# BT-5.net
KiCad netlist of a schematic drawn in EAGLE
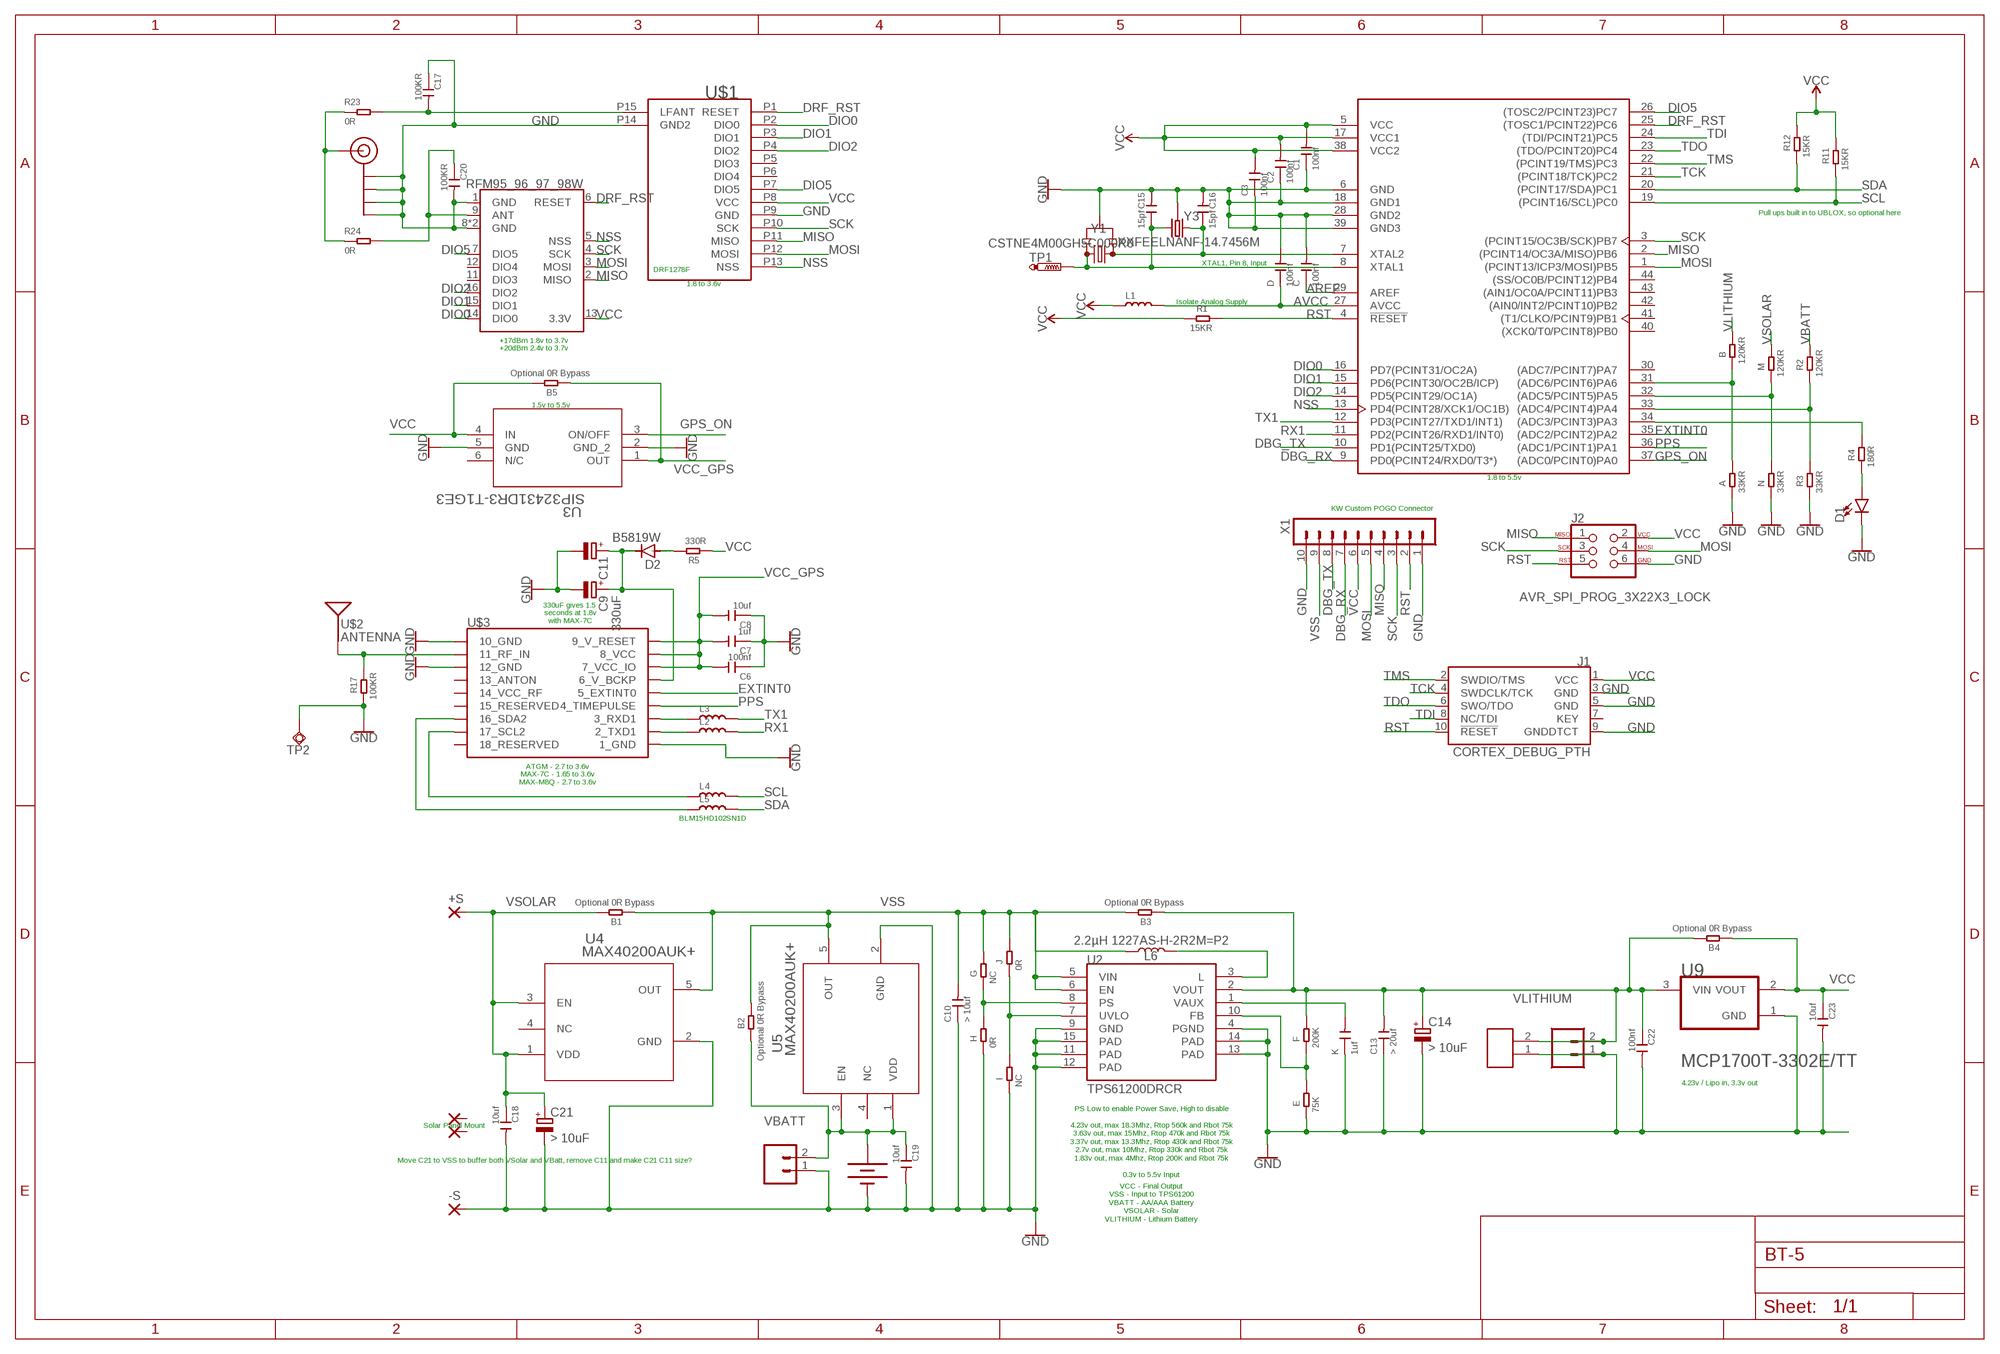
[diagram p0: schematic, sheet 1]

(export (version "E")
  (design (tool "Eeschema 10.0.6"))
  (components
    (comp (ref "+S")
      (value "SMD2")
      (footprint "eagle-import:SMD1,27-2,54")
      (libsource (lib "eagle-import") (part "SMD2"))
    )
    (comp (ref "-S")
      (value "SMD2")
      (footprint "eagle-import:SMD1,27-2,54")
      (libsource (lib "eagle-import") (part "SMD2"))
    )
    (comp (ref "A")
      (value "33KR")
      (footprint "eagle-import:R0402")
      (fields (field (name "MPN") "RC0402JR-070RL"))
      (libsource (lib "eagle-import") (part "SMD-RES-20K-5%-1/16W(0402)"))
    )
    (comp (ref "B")
      (value "120KR")
      (footprint "eagle-import:R0402")
      (fields (field (name "MPN") "RC0402JR-070RL"))
      (libsource (lib "eagle-import") (part "SMD-RES-20K-5%-1/16W(0402)"))
    )
    (comp (ref "B1")
      (value "Optional 0R Bypass")
      (footprint "eagle-import:R0402")
      (fields (field (name "MPN") "RC0402JR-070RL"))
      (libsource (lib "eagle-import") (part "SMD-RES-20K-5%-1/16W(0402)"))
    )
    (comp (ref "B2")
      (value "Optional 0R Bypass")
      (footprint "eagle-import:R0402")
      (fields (field (name "MPN") "RC0402JR-070RL"))
      (libsource (lib "eagle-import") (part "SMD-RES-20K-5%-1/16W(0402)"))
    )
    (comp (ref "B3")
      (value "Optional 0R Bypass")
      (footprint "eagle-import:R0402")
      (fields (field (name "MPN") "RC0402JR-070RL"))
      (libsource (lib "eagle-import") (part "SMD-RES-20K-5%-1/16W(0402)"))
    )
    (comp (ref "B4")
      (value "Optional 0R Bypass")
      (footprint "eagle-import:R0402")
      (fields (field (name "MPN") "RC0402JR-070RL"))
      (libsource (lib "eagle-import") (part "SMD-RES-20K-5%-1/16W(0402)"))
    )
    (comp (ref "B5")
      (value "Optional 0R Bypass")
      (footprint "eagle-import:R0402")
      (fields (field (name "MPN") "RC0402JR-070RL"))
      (libsource (lib "eagle-import") (part "SMD-RES-20K-5%-1/16W(0402)"))
    )
    (comp (ref "BT1")
      (value "BATTERY")
      (footprint "eagle-import:BATTERY-AA-AAA")
      (libsource (lib "eagle-import") (part "BATTERY"))
    )
    (comp (ref "C")
      (value "100nf")
      (footprint "eagle-import:C0402")
      (fields (field (name "MPN") "CC0402KRX7R8BB104"))
      (libsource (lib "eagle-import") (part "CERAMIC-100NF-25V-10%-X7R(0402)"))
    )
    (comp (ref "C1")
      (value "100nf")
      (footprint "eagle-import:C0402")
      (fields (field (name "MPN") "CC0402KRX7R8BB104"))
      (libsource (lib "eagle-import") (part "CERAMIC-100NF-25V-10%-X7R(0402)"))
    )
    (comp (ref "C2")
      (value "100nf")
      (footprint "eagle-import:C0402")
      (fields (field (name "MPN") "CC0402KRX7R8BB104"))
      (libsource (lib "eagle-import") (part "CERAMIC-100NF-25V-10%-X7R(0402)"))
    )
    (comp (ref "C3")
      (value "100nf")
      (footprint "eagle-import:C0402")
      (fields (field (name "MPN") "CC0402KRX7R8BB104"))
      (libsource (lib "eagle-import") (part "CERAMIC-100NF-25V-10%-X7R(0402)"))
    )
    (comp (ref "C6")
      (value "100nf")
      (footprint "eagle-import:C0402")
      (fields (field (name "MPN") "CC0402KRX7R8BB104"))
      (libsource (lib "eagle-import") (part "CERAMIC-100NF-25V-10%-X7R(0402)"))
    )
    (comp (ref "C7")
      (value "1uf")
      (footprint "eagle-import:C0402")
      (fields (field (name "MPN") "CC0402KRX5R6BB105"))
      (libsource (lib "eagle-import") (part "CERAMIC-1UF-10V-10%-X5R(0402)"))
    )
    (comp (ref "C8")
      (value "10uf")
      (footprint "eagle-import:C0402")
      (fields (field (name "MPN") "CC0402MRX5R5BB106"))
      (libsource (lib "eagle-import") (part "CERAMIC-10UF-6.3V-20%-X5R(0402)"))
    )
    (comp (ref "C9")
      (value "330uF")
      (footprint "eagle-import:RCL_SMC_C")
      (libsource (lib "eagle-import") (part "RCL_CPOL-EUSMCC"))
    )
    (comp (ref "C10")
      (value "> 10uf")
      (footprint "eagle-import:C0603")
      (fields (field (name "MPN") "CC0603KRX5R6BB106"))
      (libsource (lib "eagle-import") (part "CERAMIC-10UF-10V-10%-X5R(0603)"))
    )
    (comp (ref "C11")
      (value "C-POL_ECAP-10.5MM")
      (footprint "eagle-import:CAPAE1030X1050N")
      (libsource (lib "eagle-import") (part "C-POLECAP-10.5MM_"))
    )
    (comp (ref "C13")
      (value "> 20uf")
      (footprint "eagle-import:C0603")
      (fields (field (name "MPN") "CC0603KRX5R6BB106"))
      (libsource (lib "eagle-import") (part "CERAMIC-10UF-10V-10%-X5R(0603)"))
    )
    (comp (ref "C14")
      (value "> 10uF")
      (footprint "eagle-import:RCL_SMC_C")
      (libsource (lib "eagle-import") (part "RCL_CPOL-EUSMCC"))
    )
    (comp (ref "C15")
      (value "15pf")
      (footprint "eagle-import:C0402")
      (fields (field (name "MPN") "CC0402KRX7R8BB104"))
      (libsource (lib "eagle-import") (part "CERAMIC-100NF-25V-10%-X7R(0402)"))
    )
    (comp (ref "C16")
      (value "15pf")
      (footprint "eagle-import:C0402")
      (fields (field (name "MPN") "CC0402KRX7R8BB104"))
      (libsource (lib "eagle-import") (part "CERAMIC-100NF-25V-10%-X7R(0402)"))
    )
    (comp (ref "C17")
      (value "100KR")
      (footprint "eagle-import:C0402")
      (fields (field (name "MPN") "CC0402MRX5R5BB106"))
      (libsource (lib "eagle-import") (part "CERAMIC-10UF-6.3V-20%-X5R(0402)"))
    )
    (comp (ref "C18")
      (value "10uf")
      (footprint "eagle-import:C0402")
      (fields (field (name "MPN") "CC0402MRX5R5BB106"))
      (libsource (lib "eagle-import") (part "CERAMIC-10UF-6.3V-20%-X5R(0402)"))
    )
    (comp (ref "C19")
      (value "10uf")
      (footprint "eagle-import:C0402")
      (fields (field (name "MPN") "CC0402MRX5R5BB106"))
      (libsource (lib "eagle-import") (part "CERAMIC-10UF-6.3V-20%-X5R(0402)"))
    )
    (comp (ref "C20")
      (value "100KR")
      (footprint "eagle-import:C0402")
      (fields (field (name "MPN") "CC0402MRX5R5BB106"))
      (libsource (lib "eagle-import") (part "CERAMIC-10UF-6.3V-20%-X5R(0402)"))
    )
    (comp (ref "C21")
      (value "> 10uF")
      (footprint "eagle-import:RCL_SMC_C")
      (libsource (lib "eagle-import") (part "RCL_CPOL-EUSMCC"))
    )
    (comp (ref "C22")
      (value "100nf")
      (footprint "eagle-import:C0402")
      (fields (field (name "MPN") "CC0402KRX7R8BB104"))
      (libsource (lib "eagle-import") (part "CERAMIC-100NF-25V-10%-X7R(0402)"))
    )
    (comp (ref "C23")
      (value "10uf")
      (footprint "eagle-import:C0402")
      (fields (field (name "MPN") "CC0402MRX5R5BB106"))
      (libsource (lib "eagle-import") (part "CERAMIC-10UF-6.3V-20%-X5R(0402)"))
    )
    (comp (ref "D")
      (value "100nf")
      (footprint "eagle-import:C0402")
      (fields (field (name "MPN") "CC0402KRX7R8BB104"))
      (libsource (lib "eagle-import") (part "CERAMIC-100NF-25V-10%-X7R(0402)"))
    )
    (comp (ref "D1")
      (value "LED0603")
      (footprint "eagle-import:LED-0603")
      (libsource (lib "eagle-import") (part "LED0603"))
    )
    (comp (ref "D2")
      (value "B5819W")
      (footprint "eagle-import:SOD123")
      (fields (field (name "LCSC_PART") "C8598"))
      (libsource (lib "eagle-import") (part "DIODE-SOD123"))
    )
    (comp (ref "E")
      (value "75K")
      (footprint "eagle-import:R0402")
      (fields (field (name "MPN") "RC0402JR-070RL"))
      (libsource (lib "eagle-import") (part "SMD-RES-20K-5%-1/16W(0402)"))
    )
    (comp (ref "F")
      (value "200K")
      (footprint "eagle-import:R0402")
      (fields (field (name "MPN") "RC0402JR-070RL"))
      (libsource (lib "eagle-import") (part "SMD-RES-20K-5%-1/16W(0402)"))
    )
    (comp (ref "G")
      (value "NC")
      (footprint "eagle-import:R0402")
      (fields (field (name "MPN") "RC0402JR-070RL"))
      (libsource (lib "eagle-import") (part "SMD-RES-20K-5%-1/16W(0402)"))
    )
    (comp (ref "H")
      (value "0R")
      (footprint "eagle-import:R0402")
      (fields (field (name "MPN") "RC0402JR-070RL"))
      (libsource (lib "eagle-import") (part "SMD-RES-20K-5%-1/16W(0402)"))
    )
    (comp (ref "I")
      (value "NC")
      (footprint "eagle-import:R0402")
      (fields (field (name "MPN") "RC0402JR-070RL"))
      (libsource (lib "eagle-import") (part "SMD-RES-20K-5%-1/16W(0402)"))
    )
    (comp (ref "J")
      (value "0R")
      (footprint "eagle-import:R0402")
      (fields (field (name "MPN") "RC0402JR-070RL"))
      (libsource (lib "eagle-import") (part "SMD-RES-20K-5%-1/16W(0402)"))
    )
    (comp (ref "J$1")
      (value "SMA_EDGE")
      (footprint "eagle-import:SMA-EDGE")
      (libsource (lib "eagle-import") (part "SMA_EDGE"))
    )
    (comp (ref "J1")
      (value "CORTEX_DEBUG_PTH")
      (footprint "eagle-import:2X5-PTH-1.27MM")
      (libsource (lib "eagle-import") (part "CORTEX_DEBUG_PTH"))
    )
    (comp (ref "J2")
      (value "AVR_SPI_PROG_3X22X3_LOCK")
      (footprint "eagle-import:2X3_LOCK")
      (libsource (lib "eagle-import") (part "AVR_SPI_PROG_3X22X3_LOCK"))
    )
    (comp (ref "J4")
      (value "CONN_02JST-PTH-2-KIT")
      (footprint "eagle-import:JST-2-PTH-KIT")
      (libsource (lib "eagle-import") (part "CONN_02JST-PTH-2-KIT"))
    )
    (comp (ref "J5")
      (value "JST_ZH_2PIN")
      (footprint "eagle-import:JST_ZH_2PIN")
      (libsource (lib "eagle-import") (part "JST_ZH_2PIN"))
    )
    (comp (ref "J6")
      (value "CONN_02JST-PTH-2-KIT")
      (footprint "eagle-import:JST-2-PTH-KIT")
      (libsource (lib "eagle-import") (part "CONN_02JST-PTH-2-KIT"))
    )
    (comp (ref "K")
      (value "1uf")
      (footprint "eagle-import:C0402")
      (fields (field (name "MPN") "CC0402KRX5R6BB105"))
      (libsource (lib "eagle-import") (part "CERAMIC-1UF-10V-10%-X5R(0402)"))
    )
    (comp (ref "L1")
      (value "BLM15HD102SN1D")
      (footprint "eagle-import:L0402")
      (libsource (lib "eagle-import") (part "SMD-INDUCTOR-3.3NH-0.3NH-300MA(0402)"))
    )
    (comp (ref "L2")
      (value "BLM15HD102SN1D")
      (footprint "eagle-import:L0402")
      (libsource (lib "eagle-import") (part "SMD-INDUCTOR-3.3NH-0.3NH-300MA(0402)"))
    )
    (comp (ref "L3")
      (value "BLM15HD102SN1D")
      (footprint "eagle-import:L0402")
      (libsource (lib "eagle-import") (part "SMD-INDUCTOR-3.3NH-0.3NH-300MA(0402)"))
    )
    (comp (ref "L4")
      (value "BLM15HD102SN1D")
      (footprint "eagle-import:L0402")
      (libsource (lib "eagle-import") (part "SMD-INDUCTOR-3.3NH-0.3NH-300MA(0402)"))
    )
    (comp (ref "L5")
      (value "BLM15HD102SN1D")
      (footprint "eagle-import:L0402")
      (libsource (lib "eagle-import") (part "SMD-INDUCTOR-3.3NH-0.3NH-300MA(0402)"))
    )
    (comp (ref "L6")
      (value "2.2µH 1227AS-H-2R2M=P2")
      (footprint "eagle-import:INDUCTOR_4.7UH")
      (fields (field (name "LCSC_PART") "C435389"))
      (libsource (lib "eagle-import") (part "INDUCTOR-CDRH-4.7UH"))
    )
    (comp (ref "M")
      (value "120KR")
      (footprint "eagle-import:R0402")
      (fields (field (name "MPN") "RC0402JR-070RL"))
      (libsource (lib "eagle-import") (part "SMD-RES-20K-5%-1/16W(0402)"))
    )
    (comp (ref "N")
      (value "33KR")
      (footprint "eagle-import:R0402")
      (fields (field (name "MPN") "RC0402JR-070RL"))
      (libsource (lib "eagle-import") (part "SMD-RES-20K-5%-1/16W(0402)"))
    )
    (comp (ref "NC1")
      (value "SMD2")
      (footprint "eagle-import:SMD1,27-2,54")
      (libsource (lib "eagle-import") (part "SMD2"))
    )
    (comp (ref "NC2")
      (value "SMD2")
      (footprint "eagle-import:SMD1,27-2,54")
      (libsource (lib "eagle-import") (part "SMD2"))
    )
    (comp (ref "R1")
      (value "15KR")
      (footprint "eagle-import:R0402")
      (fields (field (name "MPN") "RC0402JR-070RL"))
      (libsource (lib "eagle-import") (part "SMD-RES-20K-5%-1/16W(0402)"))
    )
    (comp (ref "R2")
      (value "120KR")
      (footprint "eagle-import:R0402")
      (fields (field (name "MPN") "RC0402JR-070RL"))
      (libsource (lib "eagle-import") (part "SMD-RES-20K-5%-1/16W(0402)"))
    )
    (comp (ref "R3")
      (value "33KR")
      (footprint "eagle-import:R0402")
      (fields (field (name "MPN") "RC0402JR-070RL"))
      (libsource (lib "eagle-import") (part "SMD-RES-20K-5%-1/16W(0402)"))
    )
    (comp (ref "R4")
      (value "180R")
      (footprint "eagle-import:R0402")
      (fields (field (name "MPN") "RC0402JR-070RL"))
      (libsource (lib "eagle-import") (part "SMD-RES-20K-5%-1/16W(0402)"))
    )
    (comp (ref "R5")
      (value "330R")
      (footprint "eagle-import:R0402")
      (fields (field (name "MPN") "RC0402JR-070RL"))
      (libsource (lib "eagle-import") (part "SMD-RES-20K-5%-1/16W(0402)"))
    )
    (comp (ref "R11")
      (value "15KR")
      (footprint "eagle-import:R0402")
      (fields (field (name "MPN") "RC0402JR-070RL"))
      (libsource (lib "eagle-import") (part "SMD-RES-20K-5%-1/16W(0402)"))
    )
    (comp (ref "R12")
      (value "15KR")
      (footprint "eagle-import:R0402")
      (fields (field (name "MPN") "RC0402JR-070RL"))
      (libsource (lib "eagle-import") (part "SMD-RES-20K-5%-1/16W(0402)"))
    )
    (comp (ref "R17")
      (value "100KR")
      (footprint "eagle-import:R0402")
      (fields (field (name "MPN") "RC0402JR-070RL"))
      (libsource (lib "eagle-import") (part "SMD-RES-20K-5%-1/16W(0402)"))
    )
    (comp (ref "R23")
      (value "0R")
      (footprint "eagle-import:R0603")
      (fields (field (name "MPN") "RC0603FR-071K5L"))
      (libsource (lib "eagle-import") (part "SMD-RES-0R-1%-1/10W(0603)"))
    )
    (comp (ref "R24")
      (value "0R")
      (footprint "eagle-import:R0603")
      (fields (field (name "MPN") "RC0603FR-071K5L"))
      (libsource (lib "eagle-import") (part "SMD-RES-0R-1%-1/10W(0603)"))
    )
    (comp (ref "TP1")
      (value "TESTPAD_PTR1TP10R")
      (footprint "eagle-import:TESTPAD_TP10R")
      (libsource (lib "eagle-import") (part "TESTPAD_PTR1TP10R"))
    )
    (comp (ref "TP2")
      (value "TPSQTP08SQ")
      (footprint "eagle-import:TP08SQ")
      (libsource (lib "eagle-import") (part "TPSQTP08SQ"))
    )
    (comp (ref "U$1")
      (value "DRF1278F")
      (footprint "eagle-import:DRF1278F_2_NO_PINS")
      (libsource (lib "eagle-import") (part "DRF1278F_2NO_PINS"))
    )
    (comp (ref "U$2")
      (value "ANTENNA")
      (footprint "eagle-import:ANT-GPS-3X10MM")
      (libsource (lib "eagle-import") (part "ANTENNA"))
    )
    (comp (ref "U$3")
      (value "AVA_UBLOX_MAX-6")
      (footprint "eagle-import:AVA_UBLOX_MAX-6")
      (libsource (lib "eagle-import") (part "AVA_UBLOX_MAX-6"))
    )
    (comp (ref "U1")
      (value "ATMEGA1284P-AU")
      (footprint "eagle-import:TQFP-44")
      (fields
        (field (name "DIGIKEY_PART_NUMBER") "ATMEGA1284P-AU-ND")
        (field (name "MANUFACTURER") "Microchip Technology")
        (field (name "LCSC_PART") "C33575")
        (field (name "CREATED_BY") "PCBLayout.com")
      )
      (libsource (lib "eagle-import") (part "ATMEGA1284P-AU"))
    )
    (comp (ref "U2")
      (value "TPS61200DRCR")
      (footprint "eagle-import:QFN-10_PAD")
      (fields (field (name "LCSC_PART") "C140320"))
      (libsource (lib "eagle-import") (part "TPS61200"))
    )
    (comp (ref "U3")
      (value "SIP32431DR3-T1GE3")
      (footprint "eagle-import:SC-70-6_VIS")
      (fields
        (field (name "LCSC_PART") "C141606")
        (field (name "COPYRIGHT") "Copyright (C) 2018 Accelerated Designs. All rights reserved")
      )
      (libsource (lib "eagle-import") (part "SIP32431DR3-T1GE3"))
    )
    (comp (ref "U4")
      (value "MAX40200AUK+")
      (footprint "eagle-import:RAJX_V4.5_REVA_21-0057F_MXM")
      (fields (field (name "COPYRIGHT") "Copyright (C) 2018 Accelerated Designs. All rights reserved"))
      (libsource (lib "eagle-import") (part "RAJX_V4.5_REVA_MAX40200AUK+"))
    )
    (comp (ref "U5")
      (value "MAX40200AUK+")
      (footprint "eagle-import:RAJX_V4.5_REVA_21-0057F_MXM")
      (fields (field (name "COPYRIGHT") "Copyright (C) 2018 Accelerated Designs. All rights reserved"))
      (libsource (lib "eagle-import") (part "RAJX_V4.5_REVA_MAX40200AUK+"))
    )
    (comp (ref "U6")
      (value "RFM95_96_97_98W")
      (footprint "eagle-import:RFM69HCW-XXXS2")
      (libsource (lib "eagle-import") (part "RFM69HCW-433"))
    )
    (comp (ref "U9")
      (value "MICROCHIP_MCP1700T-3302E-TTMICROCHIP_MCP1700T-3302E-TT_0_0")
      (footprint "eagle-import:MICROCHIP_MCP1700T-3302E-TT_0")
      (fields (field (name "MF") "Microchip") (field (name "MPN") "MCP1700T-3302E/TT"))
      (libsource (lib "eagle-import") (part "MICROCHIP_MCP1700T-3302E-TTMICROCHIP_MCP1700T-3302E-TT_0_0"))
    )
    (comp (ref "X1")
      (value "KEW_HF_V13_M_1R10KW_50MIL-H")
      (footprint "eagle-import:KEW_HF_V13_M_1R09_50MIL-H")
      (libsource (lib "eagle-import") (part "KEW_HF_V13_M_1R10KW_50MIL-H"))
    )
    (comp (ref "Y1")
      (value "CSTNE4M00GH5C000R0")
      (footprint "eagle-import:SPARKFUN-CLOCKS-KW_RESONATOR-SMD-3.2X1.3")
      (libsource (lib "eagle-import") (part "SPARKFUN-CLOCKS-KW_RESONATOR-8MHZSMD_3.2X1.3"))
    )
    (comp (ref "Y3")
      (value "XXFEELNANF-14.7456M")
      (footprint "eagle-import:CRYSTAL-SMD-3.2X2.5MM")
      (fields (field (name "LCSC_PART") "C124311"))
      (libsource (lib "eagle-import") (part "CRYSTAL-GROUNDEDSMD-3.2X2.5"))
    )
  )
  (nets
    (net (code "1") (name "/AREF") (class "Default")
      (node (ref "C") (pin "1") (pinfunction "1_1") (pintype "passive"))
      (node (ref "U1") (pin "29") (pinfunction "AREF_29") (pintype "input"))
    )
    (net (code "2") (name "/AVCC") (class "Default")
      (node (ref "D") (pin "1") (pinfunction "1_1") (pintype "passive"))
      (node (ref "L1") (pin "2") (pinfunction "2_2") (pintype "passive"))
      (node (ref "U1") (pin "27") (pinfunction "AVCC_27") (pintype "power_in"))
    )
    (net (code "3") (name "/DBG_RX") (class "Default")
      (node (ref "U1") (pin "9") (pinfunction "PD0(PCINT24/RXD0/T3*)_9") (pintype "bidirectional"))
      (node (ref "X1") (pin "7") (pinfunction "7_7") (pintype "bidirectional"))
    )
    (net (code "4") (name "/DBG_TX") (class "Default")
      (node (ref "U1") (pin "10") (pinfunction "PD1(PCINT25/TXD0)_10") (pintype "bidirectional"))
      (node (ref "X1") (pin "8") (pinfunction "8_8") (pintype "bidirectional"))
    )
    (net (code "5") (name "/DIO0") (class "Default")
      (node (ref "U$1") (pin "P2") (pinfunction "DIO0_P2") (pintype "bidirectional"))
      (node (ref "U1") (pin "16") (pinfunction "PD7(PCINT31/OC2A)_16") (pintype "bidirectional"))
      (node (ref "U6") (pin "14") (pinfunction "DIO0_14") (pintype "bidirectional"))
    )
    (net (code "6") (name "/DIO1") (class "Default")
      (node (ref "U$1") (pin "P3") (pinfunction "DIO1_P3") (pintype "bidirectional"))
      (node (ref "U1") (pin "15") (pinfunction "PD6(PCINT30/OC2B/ICP)_15") (pintype "bidirectional"))
      (node (ref "U6") (pin "15") (pinfunction "DIO1_15") (pintype "bidirectional"))
    )
    (net (code "7") (name "/DIO2") (class "Default")
      (node (ref "U$1") (pin "P4") (pinfunction "DIO2_P4") (pintype "bidirectional"))
      (node (ref "U1") (pin "14") (pinfunction "PD5(PCINT29/OC1A)_14") (pintype "bidirectional"))
      (node (ref "U6") (pin "16") (pinfunction "DIO2_16") (pintype "bidirectional"))
    )
    (net (code "8") (name "/DIO5") (class "Default")
      (node (ref "U$1") (pin "P7") (pinfunction "DIO5_P7") (pintype "bidirectional"))
      (node (ref "U1") (pin "26") (pinfunction "(TOSC2/PCINT23)PC7_26") (pintype "bidirectional"))
      (node (ref "U6") (pin "7") (pinfunction "DIO5_7") (pintype "bidirectional"))
    )
    (net (code "9") (name "/DRF_RST") (class "Default")
      (node (ref "U$1") (pin "P1") (pinfunction "RESET_P1") (pintype "bidirectional"))
      (node (ref "U1") (pin "25") (pinfunction "(TOSC1/PCINT22)PC6_25") (pintype "bidirectional"))
      (node (ref "U6") (pin "6") (pinfunction "RESET_6") (pintype "input"))
    )
    (net (code "10") (name "/EXTINT0") (class "Default")
      (node (ref "U$3") (pin "5_EXTINT0") (pinfunction "5_EXTINT0_5_EXTINT0") (pintype "bidirectional"))
      (node (ref "U1") (pin "35") (pinfunction "(ADC2/PCINT2)PA2_35") (pintype "bidirectional"))
    )
    (net (code "11") (name "/GPS_ON") (class "Default")
      (node (ref "U1") (pin "37") (pinfunction "(ADC0/PCINT0)PA0_37") (pintype "bidirectional"))
      (node (ref "U3") (pin "3") (pinfunction "ON/OFF_3") (pintype "passive"))
    )
    (net (code "12") (name "/MISO") (class "Default")
      (node (ref "J2") (pin "1") (pinfunction "1_1") (pintype "passive"))
      (node (ref "U$1") (pin "P11") (pinfunction "MISO_P11") (pintype "bidirectional"))
      (node (ref "U1") (pin "2") (pinfunction "(PCINT14/OC3A/MISO)PB6_2") (pintype "bidirectional"))
      (node (ref "U6") (pin "2") (pinfunction "MISO_2") (pintype "bidirectional"))
      (node (ref "X1") (pin "4") (pinfunction "4_4") (pintype "bidirectional"))
    )
    (net (code "13") (name "/MOSI") (class "Default")
      (node (ref "J2") (pin "4") (pinfunction "4_4") (pintype "passive"))
      (node (ref "U$1") (pin "P12") (pinfunction "MOSI_P12") (pintype "bidirectional"))
      (node (ref "U1") (pin "1") (pinfunction "(PCINT13/ICP3/MOSI)PB5_1") (pintype "bidirectional"))
      (node (ref "U6") (pin "3") (pinfunction "MOSI_3") (pintype "input"))
      (node (ref "X1") (pin "5") (pinfunction "5_5") (pintype "bidirectional"))
    )
    (net (code "14") (name "/NSS") (class "Default")
      (node (ref "U$1") (pin "P13") (pinfunction "NSS_P13") (pintype "bidirectional"))
      (node (ref "U1") (pin "13") (pinfunction "PD4(PCINT28/XCK1/OC1B)_13") (pintype "bidirectional"))
      (node (ref "U6") (pin "5") (pinfunction "NSS_5") (pintype "input"))
    )
    (net (code "15") (name "/PPS") (class "Default")
      (node (ref "U$3") (pin "4_TIMEPULSE") (pinfunction "4_TIMEPULSE_4_TIMEPULSE") (pintype "bidirectional"))
      (node (ref "U1") (pin "36") (pinfunction "(ADC1/PCINT1)PA1_36") (pintype "bidirectional"))
    )
    (net (code "16") (name "/RST") (class "Default")
      (node (ref "J1") (pin "10") (pinfunction "~{RESET}_10") (pintype "bidirectional"))
      (node (ref "J2") (pin "5") (pinfunction "5_5") (pintype "passive"))
      (node (ref "R1") (pin "2") (pinfunction "2_2") (pintype "passive"))
      (node (ref "U1") (pin "4") (pinfunction "~{RESET}_4") (pintype "input"))
      (node (ref "X1") (pin "2") (pinfunction "2_2") (pintype "bidirectional"))
    )
    (net (code "17") (name "/RX1") (class "Default")
      (node (ref "L2") (pin "2") (pinfunction "2_2") (pintype "passive"))
      (node (ref "U1") (pin "11") (pinfunction "PD2(PCINT26/RXD1/INT0)_11") (pintype "bidirectional"))
    )
    (net (code "18") (name "/SCK") (class "Default")
      (node (ref "J2") (pin "3") (pinfunction "3_3") (pintype "passive"))
      (node (ref "U$1") (pin "P10") (pinfunction "SCK_P10") (pintype "bidirectional"))
      (node (ref "U1") (pin "3") (pinfunction "(PCINT15/OC3B/SCK)PB7_3") (pintype "bidirectional"))
      (node (ref "U6") (pin "4") (pinfunction "SCK_4") (pintype "input"))
      (node (ref "X1") (pin "3") (pinfunction "3_3") (pintype "bidirectional"))
    )
    (net (code "19") (name "/SCL") (class "Default")
      (node (ref "L4") (pin "2") (pinfunction "2_2") (pintype "passive"))
      (node (ref "R11") (pin "1") (pinfunction "1_1") (pintype "passive"))
      (node (ref "U1") (pin "19") (pinfunction "(PCINT16/SCL)PC0_19") (pintype "bidirectional"))
    )
    (net (code "20") (name "/SDA") (class "Default")
      (node (ref "L5") (pin "2") (pinfunction "2_2") (pintype "passive"))
      (node (ref "R12") (pin "1") (pinfunction "1_1") (pintype "passive"))
      (node (ref "U1") (pin "20") (pinfunction "(PCINT17/SDA)PC1_20") (pintype "bidirectional"))
    )
    (net (code "21") (name "/TCK") (class "Default")
      (node (ref "J1") (pin "4") (pinfunction "SWDCLK/TCK_4") (pintype "bidirectional"))
      (node (ref "U1") (pin "21") (pinfunction "(PCINT18/TCK)PC2_21") (pintype "bidirectional"))
    )
    (net (code "22") (name "/TDI") (class "Default")
      (node (ref "J1") (pin "8") (pinfunction "NC/TDI_8") (pintype "bidirectional"))
      (node (ref "U1") (pin "24") (pinfunction "(TDI/PCINT21)PC5_24") (pintype "bidirectional"))
    )
    (net (code "23") (name "/TDO") (class "Default")
      (node (ref "J1") (pin "6") (pinfunction "SWO/TDO_6") (pintype "bidirectional"))
      (node (ref "U1") (pin "23") (pinfunction "(TDO/PCINT20)PC4_23") (pintype "bidirectional"))
    )
    (net (code "24") (name "/TMS") (class "Default")
      (node (ref "J1") (pin "2") (pinfunction "SWDIO/TMS_2") (pintype "bidirectional"))
      (node (ref "U1") (pin "22") (pinfunction "(PCINT19/TMS)PC3_22") (pintype "bidirectional"))
    )
    (net (code "25") (name "/TX1") (class "Default")
      (node (ref "L3") (pin "2") (pinfunction "2_2") (pintype "passive"))
      (node (ref "U1") (pin "12") (pinfunction "PD3(PCINT27/TXD1/INT1)_12") (pintype "bidirectional"))
    )
    (net (code "26") (name "/VBATT") (class "Default")
      (node (ref "B2") (pin "1") (pinfunction "1_1") (pintype "passive"))
      (node (ref "BT1") (pin "P$1") (pinfunction "+_P$1") (pintype "power_in"))
      (node (ref "BT1") (pin "P$3") (pinfunction "+_P$3") (pintype "power_in"))
      (node (ref "BT1") (pin "P$5") (pinfunction "+_P$5") (pintype "power_in"))
      (node (ref "BT1") (pin "P$6") (pinfunction "+_P$6") (pintype "power_in"))
      (node (ref "C19") (pin "1") (pinfunction "1_1") (pintype "passive"))
      (node (ref "J4") (pin "2") (pinfunction "2_2") (pintype "passive"))
      (node (ref "R2") (pin "2") (pinfunction "2_2") (pintype "passive"))
      (node (ref "U5") (pin "1") (pinfunction "VDD_1") (pintype "power_in"))
      (node (ref "U5") (pin "3") (pinfunction "EN_3") (pintype "passive"))
    )
    (net (code "27") (name "/VCC_GPS") (class "Default")
      (node (ref "B5") (pin "1") (pinfunction "1_1") (pintype "passive"))
      (node (ref "C6") (pin "2") (pinfunction "2_2") (pintype "passive"))
      (node (ref "C7") (pin "2") (pinfunction "2_2") (pintype "passive"))
      (node (ref "C8") (pin "2") (pinfunction "2_2") (pintype "passive"))
      (node (ref "U$3") (pin "7_VCC_IO") (pinfunction "7_VCC_IO_7_VCC_IO") (pintype "power_in"))
      (node (ref "U$3") (pin "8_VCC") (pinfunction "8_VCC_8_VCC") (pintype "power_in"))
      (node (ref "U$3") (pin "9_V_RESET") (pinfunction "9_V_RESET_9_V_RESET") (pintype "power_in"))
      (node (ref "U3") (pin "1") (pinfunction "OUT_1") (pintype "output"))
    )
    (net (code "28") (name "/VLITHIUM") (class "Default")
      (node (ref "B") (pin "2") (pinfunction "2_2") (pintype "passive"))
      (node (ref "B3") (pin "1") (pinfunction "1_1") (pintype "passive"))
      (node (ref "B4") (pin "2") (pinfunction "2_2") (pintype "passive"))
      (node (ref "C13") (pin "2") (pinfunction "2_2") (pintype "passive"))
      (node (ref "C14") (pin "+") (pinfunction "+_+") (pintype "passive"))
      (node (ref "C22") (pin "1") (pinfunction "1_1") (pintype "passive"))
      (node (ref "F") (pin "2") (pinfunction "2_2") (pintype "passive"))
      (node (ref "J5") (pin "2") (pinfunction "P$2_2") (pintype "bidirectional"))
      (node (ref "J6") (pin "2") (pinfunction "2_2") (pintype "passive"))
      (node (ref "U2") (pin "2") (pinfunction "VOUT_2") (pintype "passive"))
      (node (ref "U9") (pin "3") (pinfunction "VIN_3") (pintype "power_in"))
    )
    (net (code "29") (name "/VSOLAR") (class "Default")
      (node (ref "+S") (pin "1") (pinfunction "P_1") (pintype "passive"))
      (node (ref "B1") (pin "2") (pinfunction "2_2") (pintype "passive"))
      (node (ref "C18") (pin "1") (pinfunction "1_1") (pintype "passive"))
      (node (ref "C21") (pin "+") (pinfunction "+_+") (pintype "passive"))
      (node (ref "M") (pin "2") (pinfunction "2_2") (pintype "passive"))
      (node (ref "U4") (pin "1") (pinfunction "VDD_1") (pintype "power_in"))
      (node (ref "U4") (pin "3") (pinfunction "EN_3") (pintype "passive"))
    )
    (net (code "30") (name "/VSS") (class "Default")
      (node (ref "B1") (pin "1") (pinfunction "1_1") (pintype "passive"))
      (node (ref "B2") (pin "2") (pinfunction "2_2") (pintype "passive"))
      (node (ref "B3") (pin "2") (pinfunction "2_2") (pintype "passive"))
      (node (ref "C10") (pin "2") (pinfunction "2_2") (pintype "passive"))
      (node (ref "G") (pin "2") (pinfunction "2_2") (pintype "passive"))
      (node (ref "J") (pin "2") (pinfunction "2_2") (pintype "passive"))
      (node (ref "L6") (pin "P$1") (pinfunction "1_P$1") (pintype "passive"))
      (node (ref "U2") (pin "5") (pinfunction "VIN_5") (pintype "power_in"))
      (node (ref "U2") (pin "6") (pinfunction "EN_6") (pintype "input"))
      (node (ref "U4") (pin "5") (pinfunction "OUT_5") (pintype "output"))
      (node (ref "U5") (pin "5") (pinfunction "OUT_5") (pintype "output"))
      (node (ref "X1") (pin "9") (pinfunction "9_9") (pintype "bidirectional"))
    )
    (net (code "31") (name "GND") (class "Default")
      (node (ref "-S") (pin "1") (pinfunction "P_1") (pintype "passive"))
      (node (ref "A") (pin "1") (pinfunction "1_1") (pintype "passive"))
      (node (ref "BT1") (pin "P$2") (pinfunction "-_P$2") (pintype "power_in"))
      (node (ref "BT1") (pin "P$4") (pinfunction "-_P$4") (pintype "power_in"))
      (node (ref "BT1") (pin "P$7") (pinfunction "-_P$7") (pintype "power_in"))
      (node (ref "BT1") (pin "P$8") (pinfunction "-_P$8") (pintype "power_in"))
      (node (ref "C") (pin "2") (pinfunction "2_2") (pintype "passive"))
      (node (ref "C1") (pin "1") (pinfunction "1_1") (pintype "passive"))
      (node (ref "C10") (pin "1") (pinfunction "1_1") (pintype "passive"))
      (node (ref "C11") (pin "2") (pinfunction "-_2") (pintype "passive"))
      (node (ref "C13") (pin "1") (pinfunction "1_1") (pintype "passive"))
      (node (ref "C14") (pin "-") (pinfunction "-_-") (pintype "passive"))
      (node (ref "C15") (pin "2") (pinfunction "2_2") (pintype "passive"))
      (node (ref "C16") (pin "2") (pinfunction "2_2") (pintype "passive"))
      (node (ref "C17") (pin "1") (pinfunction "1_1") (pintype "passive"))
      (node (ref "C18") (pin "2") (pinfunction "2_2") (pintype "passive"))
      (node (ref "C19") (pin "2") (pinfunction "2_2") (pintype "passive"))
      (node (ref "C2") (pin "1") (pinfunction "1_1") (pintype "passive"))
      (node (ref "C20") (pin "2") (pinfunction "2_2") (pintype "passive"))
      (node (ref "C21") (pin "-") (pinfunction "-_-") (pintype "passive"))
      (node (ref "C22") (pin "2") (pinfunction "2_2") (pintype "passive"))
      (node (ref "C23") (pin "2") (pinfunction "2_2") (pintype "passive"))
      (node (ref "C3") (pin "1") (pinfunction "1_1") (pintype "passive"))
      (node (ref "C6") (pin "1") (pinfunction "1_1") (pintype "passive"))
      (node (ref "C7") (pin "1") (pinfunction "1_1") (pintype "passive"))
      (node (ref "C8") (pin "1") (pinfunction "1_1") (pintype "passive"))
      (node (ref "C9") (pin "-") (pinfunction "-_-") (pintype "passive"))
      (node (ref "D") (pin "2") (pinfunction "2_2") (pintype "passive"))
      (node (ref "D1") (pin "C") (pinfunction "C_C") (pintype "passive"))
      (node (ref "E") (pin "1") (pinfunction "1_1") (pintype "passive"))
      (node (ref "H") (pin "1") (pinfunction "1_1") (pintype "passive"))
      (node (ref "I") (pin "1") (pinfunction "1_1") (pintype "passive"))
      (node (ref "J$1") (pin "GND@0") (pinfunction "GND_GND@0") (pintype "bidirectional"))
      (node (ref "J$1") (pin "GND@1") (pinfunction "GND_GND@1") (pintype "bidirectional"))
      (node (ref "J$1") (pin "GND@2") (pinfunction "GND_GND@2") (pintype "bidirectional"))
      (node (ref "J$1") (pin "GND@3") (pinfunction "GND_GND@3") (pintype "bidirectional"))
      (node (ref "J1") (pin "3") (pinfunction "GND_3") (pintype "bidirectional"))
      (node (ref "J1") (pin "5") (pinfunction "GND_5") (pintype "bidirectional"))
      (node (ref "J1") (pin "9") (pinfunction "GNDDTCT_9") (pintype "bidirectional"))
      (node (ref "J2") (pin "6") (pinfunction "6_6") (pintype "passive"))
      (node (ref "J4") (pin "1") (pinfunction "1_1") (pintype "passive"))
      (node (ref "J5") (pin "1") (pinfunction "P$1_1") (pintype "bidirectional"))
      (node (ref "J6") (pin "1") (pinfunction "1_1") (pintype "passive"))
      (node (ref "K") (pin "1") (pinfunction "1_1") (pintype "passive"))
      (node (ref "N") (pin "1") (pinfunction "1_1") (pintype "passive"))
      (node (ref "R17") (pin "1") (pinfunction "1_1") (pintype "passive"))
      (node (ref "R3") (pin "1") (pinfunction "1_1") (pintype "passive"))
      (node (ref "TP2") (pin "TP") (pinfunction "TP_TP") (pintype "input"))
      (node (ref "U$1") (pin "P14") (pinfunction "GND2_P14") (pintype "bidirectional"))
      (node (ref "U$1") (pin "P9") (pinfunction "GND_P9") (pintype "bidirectional"))
      (node (ref "U$3") (pin "10_GND") (pinfunction "10_GND_10_GND") (pintype "power_in"))
      (node (ref "U$3") (pin "12_GND") (pinfunction "12_GND_12_GND") (pintype "power_in"))
      (node (ref "U$3") (pin "1_GND") (pinfunction "1_GND_1_GND") (pintype "power_in"))
      (node (ref "U1") (pin "18") (pinfunction "GND1_18") (pintype "power_in"))
      (node (ref "U1") (pin "28") (pinfunction "GND2_28") (pintype "power_in"))
      (node (ref "U1") (pin "39") (pinfunction "GND3_39") (pintype "power_in"))
      (node (ref "U1") (pin "6") (pinfunction "GND_6") (pintype "power_in"))
      (node (ref "U2") (pin "11") (pinfunction "PAD_11") (pintype "power_in"))
      (node (ref "U2") (pin "12") (pinfunction "PAD_12") (pintype "power_in"))
      (node (ref "U2") (pin "13") (pinfunction "PAD_13") (pintype "power_in"))
      (node (ref "U2") (pin "14") (pinfunction "PAD_14") (pintype "power_in"))
      (node (ref "U2") (pin "15") (pinfunction "PAD_15") (pintype "power_in"))
      (node (ref "U2") (pin "4") (pinfunction "PGND_4") (pintype "power_in"))
      (node (ref "U2") (pin "9") (pinfunction "GND_9") (pintype "power_in"))
      (node (ref "U3") (pin "2") (pinfunction "GND_2_2") (pintype "passive"))
      (node (ref "U3") (pin "5") (pinfunction "GND_5") (pintype "passive"))
      (node (ref "U4") (pin "2") (pinfunction "GND_2") (pintype "passive"))
      (node (ref "U5") (pin "2") (pinfunction "GND_2") (pintype "passive"))
      (node (ref "U6") (pin "1") (pinfunction "GND_1") (pintype "power_in"))
      (node (ref "U6") (pin "10") (pinfunction "GND_10") (pintype "power_in"))
      (node (ref "U6") (pin "8") (pinfunction "GND_8") (pintype "power_in"))
      (node (ref "U9") (pin "1") (pinfunction "GND_1") (pintype "power_in"))
      (node (ref "X1") (pin "1") (pinfunction "1_1") (pintype "bidirectional"))
      (node (ref "X1") (pin "10") (pinfunction "10_10") (pintype "bidirectional"))
      (node (ref "Y1") (pin "2") (pinfunction "2_2") (pintype "passive"))
      (node (ref "Y3") (pin "2") (pinfunction "3_2") (pintype "passive"))
      (node (ref "Y3") (pin "4") (pinfunction "3_4") (pintype "passive"))
    )
    (net (code "32") (name "Net-(C11-+)") (class "Default")
      (node (ref "C11") (pin "1") (pinfunction "+_1") (pintype "passive"))
      (node (ref "C9") (pin "+") (pinfunction "+_+") (pintype "passive"))
      (node (ref "D2") (pin "C") (pinfunction "C_C") (pintype "passive"))
      (node (ref "U$3") (pin "6_V_BCKP") (pinfunction "6_V_BCKP_6_V_BCKP") (pintype "bidirectional"))
    )
    (net (code "33") (name "Net-(D1-PadA)") (class "Default")
      (node (ref "D1") (pin "A") (pinfunction "A_A") (pintype "passive"))
      (node (ref "R4") (pin "1") (pinfunction "1_1") (pintype "passive"))
    )
    (net (code "34") (name "Net-(D2-PadA)") (class "Default")
      (node (ref "D2") (pin "A") (pinfunction "A_A") (pintype "passive"))
      (node (ref "R5") (pin "2") (pinfunction "2_2") (pintype "passive"))
    )
    (net (code "35") (name "Net-(J$1-SIGNAL)") (class "Default")
      (node (ref "J$1") (pin "SIG") (pinfunction "SIGNAL_SIG") (pintype "bidirectional"))
      (node (ref "R23") (pin "1") (pinfunction "1_1") (pintype "passive"))
      (node (ref "R24") (pin "1") (pinfunction "1_1") (pintype "passive"))
    )
    (net (code "36") (name "Net-(L2-Pad1)") (class "Default")
      (node (ref "L2") (pin "1") (pinfunction "1_1") (pintype "passive"))
      (node (ref "U$3") (pin "2_TXD1") (pinfunction "2_TXD1_2_TXD1") (pintype "bidirectional"))
    )
    (net (code "37") (name "Net-(L3-Pad1)") (class "Default")
      (node (ref "L3") (pin "1") (pinfunction "1_1") (pintype "passive"))
      (node (ref "U$3") (pin "3_RXD1") (pinfunction "3_RXD1_3_RXD1") (pintype "bidirectional"))
    )
    (net (code "38") (name "Net-(L4-Pad1)") (class "Default")
      (node (ref "L4") (pin "1") (pinfunction "1_1") (pintype "passive"))
      (node (ref "U$3") (pin "17_SCL2") (pinfunction "17_SCL2_17_SCL2") (pintype "bidirectional"))
    )
    (net (code "39") (name "Net-(L5-Pad1)") (class "Default")
      (node (ref "L5") (pin "1") (pinfunction "1_1") (pintype "passive"))
      (node (ref "U$3") (pin "16_SDA2") (pinfunction "16_SDA2_16_SDA2") (pintype "bidirectional"))
    )
    (net (code "40") (name "Net-(L6-2)") (class "Default")
      (node (ref "L6") (pin "P$2") (pinfunction "2_P$2") (pintype "passive"))
      (node (ref "U2") (pin "3") (pinfunction "L_3") (pintype "passive"))
    )
    (net (code "41") (name "Net-(U$1-LFANT)") (class "Default")
      (node (ref "C17") (pin "2") (pinfunction "2_2") (pintype "passive"))
      (node (ref "R23") (pin "2") (pinfunction "2_2") (pintype "passive"))
      (node (ref "U$1") (pin "P15") (pinfunction "LFANT_P15") (pintype "bidirectional"))
    )
    (net (code "42") (name "Net-(U$2-SIGNAL)") (class "Default")
      (node (ref "R17") (pin "2") (pinfunction "2_2") (pintype "passive"))
      (node (ref "U$2") (pin "SIG") (pinfunction "SIGNAL_SIG") (pintype "bidirectional"))
      (node (ref "U$3") (pin "11_RF_IN") (pinfunction "11_RF_IN_11_RF_IN") (pintype "bidirectional"))
    )
    (net (code "43") (name "Net-(U1-(ADC3{slash}PCINT3)PA3)") (class "Default")
      (node (ref "R4") (pin "2") (pinfunction "2_2") (pintype "passive"))
      (node (ref "U1") (pin "34") (pinfunction "(ADC3/PCINT3)PA3_34") (pintype "bidirectional"))
    )
    (net (code "44") (name "Net-(U1-(ADC4{slash}PCINT4)PA4)") (class "Default")
      (node (ref "R2") (pin "1") (pinfunction "1_1") (pintype "passive"))
      (node (ref "R3") (pin "2") (pinfunction "2_2") (pintype "passive"))
      (node (ref "U1") (pin "33") (pinfunction "(ADC4/PCINT4)PA4_33") (pintype "bidirectional"))
    )
    (net (code "45") (name "Net-(U1-(ADC5{slash}PCINT5)PA5)") (class "Default")
      (node (ref "M") (pin "1") (pinfunction "1_1") (pintype "passive"))
      (node (ref "N") (pin "2") (pinfunction "2_2") (pintype "passive"))
      (node (ref "U1") (pin "32") (pinfunction "(ADC5/PCINT5)PA5_32") (pintype "bidirectional"))
    )
    (net (code "46") (name "Net-(U1-(ADC6{slash}PCINT6)PA6)") (class "Default")
      (node (ref "A") (pin "2") (pinfunction "2_2") (pintype "passive"))
      (node (ref "B") (pin "1") (pinfunction "1_1") (pintype "passive"))
      (node (ref "U1") (pin "31") (pinfunction "(ADC6/PCINT6)PA6_31") (pintype "bidirectional"))
    )
    (net (code "47") (name "Net-(U1-XTAL1)") (class "Default")
      (node (ref "C15") (pin "1") (pinfunction "1_1") (pintype "passive"))
      (node (ref "TP1") (pin "TP") (pinfunction "TP_TP") (pintype "input"))
      (node (ref "U1") (pin "8") (pinfunction "XTAL1_8") (pintype "input"))
      (node (ref "Y1") (pin "3") (pinfunction "3_3") (pintype "passive"))
      (node (ref "Y3") (pin "3") (pinfunction "2_3") (pintype "passive"))
    )
    (net (code "48") (name "Net-(U1-XTAL2)") (class "Default")
      (node (ref "C16") (pin "1") (pinfunction "1_1") (pintype "passive"))
      (node (ref "U1") (pin "7") (pinfunction "XTAL2_7") (pintype "output"))
      (node (ref "Y1") (pin "1") (pinfunction "1_1") (pintype "passive"))
      (node (ref "Y3") (pin "1") (pinfunction "1_1") (pintype "passive"))
    )
    (net (code "49") (name "Net-(U2-FB)") (class "Default")
      (node (ref "E") (pin "2") (pinfunction "2_2") (pintype "passive"))
      (node (ref "F") (pin "1") (pinfunction "1_1") (pintype "passive"))
      (node (ref "U2") (pin "10") (pinfunction "FB_10") (pintype "passive"))
    )
    (net (code "50") (name "Net-(U2-PS)") (class "Default")
      (node (ref "G") (pin "1") (pinfunction "1_1") (pintype "passive"))
      (node (ref "H") (pin "2") (pinfunction "2_2") (pintype "passive"))
      (node (ref "U2") (pin "8") (pinfunction "PS_8") (pintype "input"))
    )
    (net (code "51") (name "Net-(U2-UVLO)") (class "Default")
      (node (ref "I") (pin "2") (pinfunction "2_2") (pintype "passive"))
      (node (ref "J") (pin "1") (pinfunction "1_1") (pintype "passive"))
      (node (ref "U2") (pin "7") (pinfunction "UVLO_7") (pintype "passive"))
    )
    (net (code "52") (name "Net-(U2-VAUX)") (class "Default")
      (node (ref "K") (pin "2") (pinfunction "2_2") (pintype "passive"))
      (node (ref "U2") (pin "1") (pinfunction "VAUX_1") (pintype "passive"))
    )
    (net (code "53") (name "Net-(U6-ANT)") (class "Default")
      (node (ref "C20") (pin "1") (pinfunction "1_1") (pintype "passive"))
      (node (ref "R24") (pin "2") (pinfunction "2_2") (pintype "passive"))
      (node (ref "U6") (pin "9") (pinfunction "ANT_9") (pintype "passive"))
    )
    (net (code "54") (name "VCC") (class "Default")
      (node (ref "B4") (pin "1") (pinfunction "1_1") (pintype "passive"))
      (node (ref "B5") (pin "2") (pinfunction "2_2") (pintype "passive"))
      (node (ref "C1") (pin "2") (pinfunction "2_2") (pintype "passive"))
      (node (ref "C2") (pin "2") (pinfunction "2_2") (pintype "passive"))
      (node (ref "C23") (pin "1") (pinfunction "1_1") (pintype "passive"))
      (node (ref "C3") (pin "2") (pinfunction "2_2") (pintype "passive"))
      (node (ref "J1") (pin "1") (pinfunction "VCC_1") (pintype "bidirectional"))
      (node (ref "J2") (pin "2") (pinfunction "2_2") (pintype "passive"))
      (node (ref "L1") (pin "1") (pinfunction "1_1") (pintype "passive"))
      (node (ref "R1") (pin "1") (pinfunction "1_1") (pintype "passive"))
      (node (ref "R11") (pin "2") (pinfunction "2_2") (pintype "passive"))
      (node (ref "R12") (pin "2") (pinfunction "2_2") (pintype "passive"))
      (node (ref "R5") (pin "1") (pinfunction "1_1") (pintype "passive"))
      (node (ref "U$1") (pin "P8") (pinfunction "VCC_P8") (pintype "bidirectional"))
      (node (ref "U1") (pin "17") (pinfunction "VCC1_17") (pintype "power_in"))
      (node (ref "U1") (pin "38") (pinfunction "VCC2_38") (pintype "power_in"))
      (node (ref "U1") (pin "5") (pinfunction "VCC_5") (pintype "power_in"))
      (node (ref "U3") (pin "4") (pinfunction "IN_4") (pintype "input"))
      (node (ref "U6") (pin "13") (pinfunction "3.3V_13") (pintype "power_in"))
      (node (ref "U9") (pin "2") (pinfunction "VOUT_2") (pintype "power_in"))
      (node (ref "X1") (pin "6") (pinfunction "6_6") (pintype "bidirectional"))
    )
    (net (code "55") (name "unconnected-(J1-KEY-Pad7)") (class "Default")
      (node (ref "J1") (pin "7") (pinfunction "KEY_7") (pintype "bidirectional"))
    )
    (net (code "56") (name "unconnected-(NC1-P-Pad1)") (class "Default")
      (node (ref "NC1") (pin "1") (pinfunction "P_1") (pintype "passive"))
    )
    (net (code "57") (name "unconnected-(NC2-P-Pad1)") (class "Default")
      (node (ref "NC2") (pin "1") (pinfunction "P_1") (pintype "passive"))
    )
    (net (code "58") (name "unconnected-(U$1-DIO3-PadP5)") (class "Default")
      (node (ref "U$1") (pin "P5") (pinfunction "DIO3_P5") (pintype "bidirectional"))
    )
    (net (code "59") (name "unconnected-(U$1-DIO4-PadP6)") (class "Default")
      (node (ref "U$1") (pin "P6") (pinfunction "DIO4_P6") (pintype "bidirectional"))
    )
    (net (code "60") (name "unconnected-(U$3-Pad13_ANTON)") (class "Default")
      (node (ref "U$3") (pin "13_ANTON") (pinfunction "13_ANTON_13_ANTON") (pintype "bidirectional"))
    )
    (net (code "61") (name "unconnected-(U$3-Pad14_VCC_RF)") (class "Default")
      (node (ref "U$3") (pin "14_VCC_RF") (pinfunction "14_VCC_RF_14_VCC_RF") (pintype "bidirectional"))
    )
    (net (code "62") (name "unconnected-(U$3-Pad15_RESERVED)") (class "Default")
      (node (ref "U$3") (pin "15_RESERVED") (pinfunction "15_RESERVED_15_RESERVED") (pintype "bidirectional"))
    )
    (net (code "63") (name "unconnected-(U$3-Pad18_RESERVED)") (class "Default")
      (node (ref "U$3") (pin "18_RESERVED") (pinfunction "18_RESERVED_18_RESERVED") (pintype "bidirectional"))
    )
    (net (code "64") (name "unconnected-(U1-(ADC7{slash}PCINT7)PA7-Pad30)") (class "Default")
      (node (ref "U1") (pin "30") (pinfunction "(ADC7/PCINT7)PA7_30") (pintype "bidirectional"))
    )
    (net (code "65") (name "unconnected-(U1-(AIN0{slash}INT2{slash}PCINT10)PB2-Pad42)") (class "Default")
      (node (ref "U1") (pin "42") (pinfunction "(AIN0/INT2/PCINT10)PB2_42") (pintype "bidirectional"))
    )
    (net (code "66") (name "unconnected-(U1-(AIN1{slash}OC0A{slash}PCINT11)PB3-Pad43)") (class "Default")
      (node (ref "U1") (pin "43") (pinfunction "(AIN1/OC0A/PCINT11)PB3_43") (pintype "bidirectional"))
    )
    (net (code "67") (name "unconnected-(U1-(SS{slash}OC0B{slash}PCINT12)PB4-Pad44)") (class "Default")
      (node (ref "U1") (pin "44") (pinfunction "(SS/OC0B/PCINT12)PB4_44") (pintype "bidirectional"))
    )
    (net (code "68") (name "unconnected-(U1-(T1{slash}CLKO{slash}PCINT9)PB1-Pad41)") (class "Default")
      (node (ref "U1") (pin "41") (pinfunction "(T1/CLKO/PCINT9)PB1_41") (pintype "bidirectional"))
    )
    (net (code "69") (name "unconnected-(U1-(XCK0{slash}T0{slash}PCINT8)PB0-Pad40)") (class "Default")
      (node (ref "U1") (pin "40") (pinfunction "(XCK0/T0/PCINT8)PB0_40") (pintype "bidirectional"))
    )
    (net (code "70") (name "unconnected-(U3-N{slash}C-Pad6)") (class "Default")
      (node (ref "U3") (pin "6") (pinfunction "N/C_6") (pintype "no_connect"))
    )
    (net (code "71") (name "unconnected-(U4-NC-Pad4)") (class "Default")
      (node (ref "U4") (pin "4") (pinfunction "NC_4") (pintype "no_connect"))
    )
    (net (code "72") (name "unconnected-(U5-NC-Pad4)") (class "Default")
      (node (ref "U5") (pin "4") (pinfunction "NC_4") (pintype "no_connect"))
    )
    (net (code "73") (name "unconnected-(U6-DIO3-Pad11)") (class "Default")
      (node (ref "U6") (pin "11") (pinfunction "DIO3_11") (pintype "bidirectional"))
    )
    (net (code "74") (name "unconnected-(U6-DIO4-Pad12)") (class "Default")
      (node (ref "U6") (pin "12") (pinfunction "DIO4_12") (pintype "bidirectional"))
    )
  )
)
